# practice.net
KiCad netlist of a schematic drawn in EAGLE
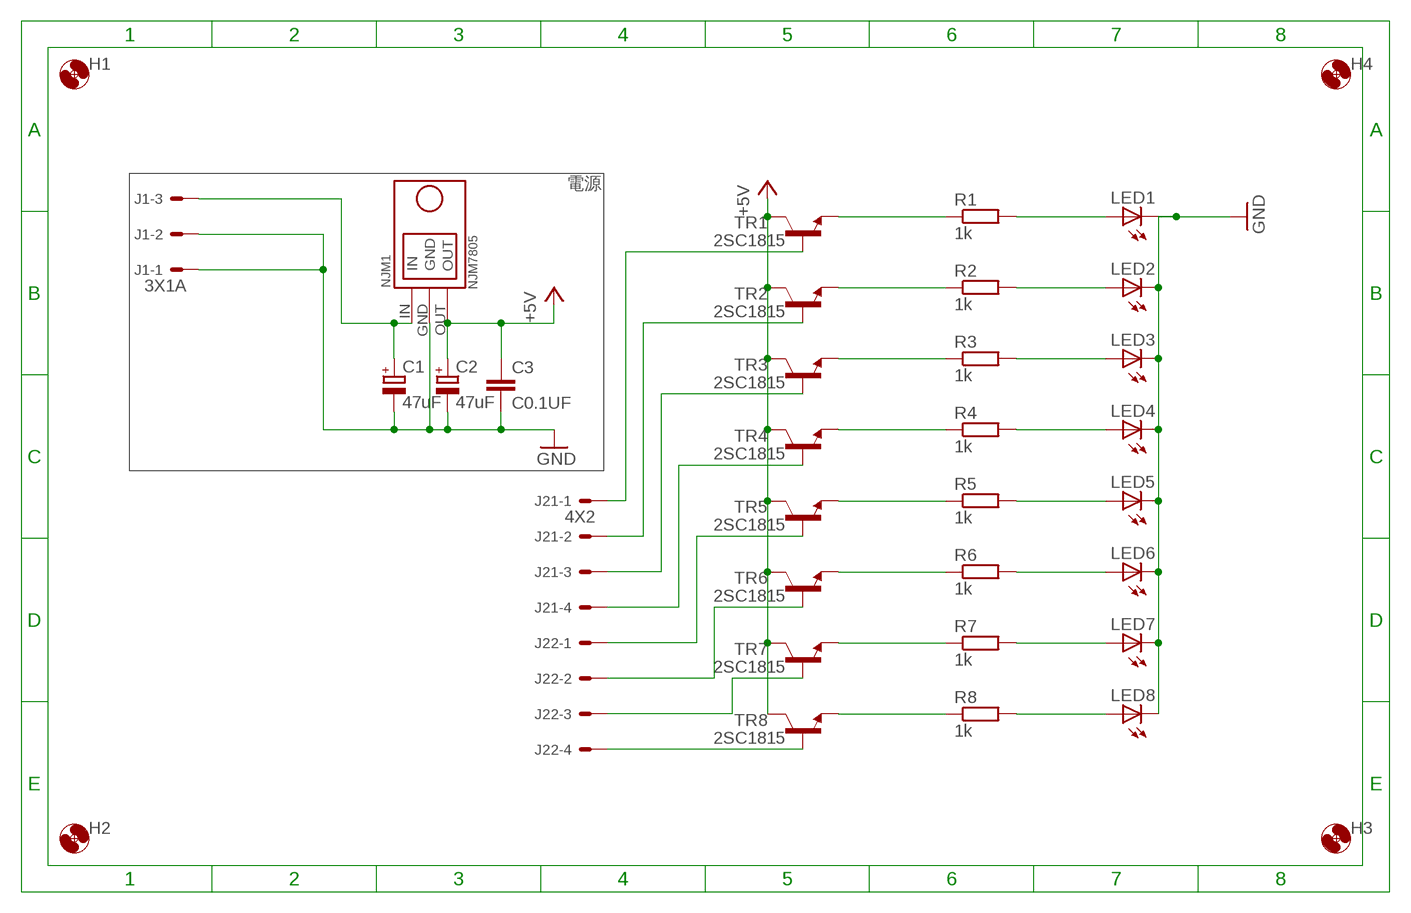
[diagram p0: schematic, sheet 1]

(export (version "E")
  (design (tool "Eeschema 10.0.6"))
  (components
    (comp (ref "C1")
      (value "47uF")
      (footprint "eagle-import:E2-5")
      (libsource (lib "eagle-import") (part "CPOL-EU2-5MM"))
    )
    (comp (ref "C2")
      (value "47uF")
      (footprint "eagle-import:E2-5")
      (libsource (lib "eagle-import") (part "CPOL-EU2-5MM"))
    )
    (comp (ref "C3")
      (value "C0.1UF")
      (footprint "eagle-import:C0.1UF")
      (libsource (lib "eagle-import") (part "C0.1UF"))
    )
    (comp (ref "H1")
      (value "HOLE3.3M3BOLT")
      (footprint "eagle-import:HOLE3.3")
      (libsource (lib "eagle-import") (part "HOLE3.3M3BOLT"))
    )
    (comp (ref "H2")
      (value "HOLE3.3M3BOLT")
      (footprint "eagle-import:HOLE3.3")
      (libsource (lib "eagle-import") (part "HOLE3.3M3BOLT"))
    )
    (comp (ref "H3")
      (value "HOLE3.3M3BOLT")
      (footprint "eagle-import:HOLE3.3")
      (libsource (lib "eagle-import") (part "HOLE3.3M3BOLT"))
    )
    (comp (ref "H4")
      (value "HOLE3.3M3BOLT")
      (footprint "eagle-import:HOLE3.3")
      (libsource (lib "eagle-import") (part "HOLE3.3M3BOLT"))
    )
    (comp (ref "J1")
      (value "3X1A")
      (footprint "eagle-import:37203-62A3-003")
      (libsource (lib "eagle-import") (part "3X1A"))
    )
    (comp (ref "J2")
      (value "4X2")
      (footprint "eagle-import:37208-62A3-004")
      (libsource (lib "eagle-import") (part "4X2"))
    )
    (comp (ref "LED1")
      (value "LED5MM")
      (footprint "eagle-import:LED5MM")
      (libsource (lib "eagle-import") (part "LED5MM"))
    )
    (comp (ref "LED2")
      (value "LED5MM")
      (footprint "eagle-import:LED5MM")
      (libsource (lib "eagle-import") (part "LED5MM"))
    )
    (comp (ref "LED3")
      (value "LED5MM")
      (footprint "eagle-import:LED5MM")
      (libsource (lib "eagle-import") (part "LED5MM"))
    )
    (comp (ref "LED4")
      (value "LED5MM")
      (footprint "eagle-import:LED5MM")
      (libsource (lib "eagle-import") (part "LED5MM"))
    )
    (comp (ref "LED5")
      (value "LED5MM")
      (footprint "eagle-import:LED5MM")
      (libsource (lib "eagle-import") (part "LED5MM"))
    )
    (comp (ref "LED6")
      (value "LED5MM")
      (footprint "eagle-import:LED5MM")
      (libsource (lib "eagle-import") (part "LED5MM"))
    )
    (comp (ref "LED7")
      (value "LED5MM")
      (footprint "eagle-import:LED5MM")
      (libsource (lib "eagle-import") (part "LED5MM"))
    )
    (comp (ref "LED8")
      (value "LED5MM")
      (footprint "eagle-import:LED5MM")
      (libsource (lib "eagle-import") (part "LED5MM"))
    )
    (comp (ref "NJM1")
      (value "NJM7805")
      (footprint "eagle-import:NJM7805")
      (libsource (lib "eagle-import") (part "NJM7805"))
    )
    (comp (ref "R1")
      (value "1k")
      (footprint "eagle-import:R3216W")
      (libsource (lib "eagle-import") (part "R-EU_R3216W"))
    )
    (comp (ref "R2")
      (value "1k")
      (footprint "eagle-import:R3216W")
      (libsource (lib "eagle-import") (part "R-EU_R3216W"))
    )
    (comp (ref "R3")
      (value "1k")
      (footprint "eagle-import:R3216W")
      (libsource (lib "eagle-import") (part "R-EU_R3216W"))
    )
    (comp (ref "R4")
      (value "1k")
      (footprint "eagle-import:R3216W")
      (libsource (lib "eagle-import") (part "R-EU_R3216W"))
    )
    (comp (ref "R5")
      (value "1k")
      (footprint "eagle-import:R3216W")
      (libsource (lib "eagle-import") (part "R-EU_R3216W"))
    )
    (comp (ref "R6")
      (value "1k")
      (footprint "eagle-import:R3216W")
      (libsource (lib "eagle-import") (part "R-EU_R3216W"))
    )
    (comp (ref "R7")
      (value "1k")
      (footprint "eagle-import:R3216W")
      (libsource (lib "eagle-import") (part "R-EU_R3216W"))
    )
    (comp (ref "R8")
      (value "1k")
      (footprint "eagle-import:R3216W")
      (libsource (lib "eagle-import") (part "R-EU_R3216W"))
    )
    (comp (ref "TR1")
      (value "2SC1815")
      (footprint "eagle-import:TO92-")
      (libsource (lib "eagle-import") (part "2SC1815"))
    )
    (comp (ref "TR2")
      (value "2SC1815")
      (footprint "eagle-import:TO92-")
      (libsource (lib "eagle-import") (part "2SC1815"))
    )
    (comp (ref "TR3")
      (value "2SC1815")
      (footprint "eagle-import:TO92-")
      (libsource (lib "eagle-import") (part "2SC1815"))
    )
    (comp (ref "TR4")
      (value "2SC1815")
      (footprint "eagle-import:TO92-")
      (libsource (lib "eagle-import") (part "2SC1815"))
    )
    (comp (ref "TR5")
      (value "2SC1815")
      (footprint "eagle-import:TO92-")
      (libsource (lib "eagle-import") (part "2SC1815"))
    )
    (comp (ref "TR6")
      (value "2SC1815")
      (footprint "eagle-import:TO92-")
      (libsource (lib "eagle-import") (part "2SC1815"))
    )
    (comp (ref "TR7")
      (value "2SC1815")
      (footprint "eagle-import:TO92-")
      (libsource (lib "eagle-import") (part "2SC1815"))
    )
    (comp (ref "TR8")
      (value "2SC1815")
      (footprint "eagle-import:TO92-")
      (libsource (lib "eagle-import") (part "2SC1815"))
    )
  )
  (nets
    (net (code "1") (name "+5V") (class "Default")
      (node (ref "C2") (pin "+") (pinfunction "+_+") (pintype "passive"))
      (node (ref "C3") (pin "1") (pinfunction "1_1") (pintype "passive"))
      (node (ref "NJM1") (pin "OUT") (pinfunction "OUT_OUT") (pintype "bidirectional"))
      (node (ref "TR1") (pin "C") (pinfunction "C_C") (pintype "passive"))
      (node (ref "TR2") (pin "C") (pinfunction "C_C") (pintype "passive"))
      (node (ref "TR3") (pin "C") (pinfunction "C_C") (pintype "passive"))
      (node (ref "TR4") (pin "C") (pinfunction "C_C") (pintype "passive"))
      (node (ref "TR5") (pin "C") (pinfunction "C_C") (pintype "passive"))
      (node (ref "TR6") (pin "C") (pinfunction "C_C") (pintype "passive"))
      (node (ref "TR7") (pin "C") (pinfunction "C_C") (pintype "passive"))
      (node (ref "TR8") (pin "C") (pinfunction "C_C") (pintype "passive"))
    )
    (net (code "2") (name "GND") (class "Default")
      (node (ref "C1") (pin "-") (pinfunction "-_-") (pintype "passive"))
      (node (ref "C2") (pin "-") (pinfunction "-_-") (pintype "passive"))
      (node (ref "C3") (pin "2") (pinfunction "2_2") (pintype "passive"))
      (node (ref "J1") (pin "1-1") (pinfunction "S_1-1") (pintype "passive"))
      (node (ref "J1") (pin "1-2") (pinfunction "S_1-2") (pintype "passive"))
      (node (ref "LED1") (pin "K") (pinfunction "C_K") (pintype "passive"))
      (node (ref "LED2") (pin "K") (pinfunction "C_K") (pintype "passive"))
      (node (ref "LED3") (pin "K") (pinfunction "C_K") (pintype "passive"))
      (node (ref "LED4") (pin "K") (pinfunction "C_K") (pintype "passive"))
      (node (ref "LED5") (pin "K") (pinfunction "C_K") (pintype "passive"))
      (node (ref "LED6") (pin "K") (pinfunction "C_K") (pintype "passive"))
      (node (ref "LED7") (pin "K") (pinfunction "C_K") (pintype "passive"))
      (node (ref "LED8") (pin "K") (pinfunction "C_K") (pintype "passive"))
      (node (ref "NJM1") (pin "GND") (pinfunction "GND_GND") (pintype "bidirectional"))
    )
    (net (code "3") (name "Net-(J1C-S)") (class "Default")
      (node (ref "C1") (pin "+") (pinfunction "+_+") (pintype "passive"))
      (node (ref "J1") (pin "1-3") (pinfunction "S_1-3") (pintype "passive"))
      (node (ref "NJM1") (pin "IN") (pinfunction "IN_IN") (pintype "bidirectional"))
    )
    (net (code "4") (name "Net-(J2A-S)") (class "Default")
      (node (ref "J2") (pin "1-1") (pinfunction "S_1-1") (pintype "passive"))
      (node (ref "TR1") (pin "B") (pinfunction "B_B") (pintype "passive"))
    )
    (net (code "5") (name "Net-(J2B-S)") (class "Default")
      (node (ref "J2") (pin "1-2") (pinfunction "S_1-2") (pintype "passive"))
      (node (ref "TR2") (pin "B") (pinfunction "B_B") (pintype "passive"))
    )
    (net (code "6") (name "Net-(J2C-S)") (class "Default")
      (node (ref "J2") (pin "1-3") (pinfunction "S_1-3") (pintype "passive"))
      (node (ref "TR3") (pin "B") (pinfunction "B_B") (pintype "passive"))
    )
    (net (code "7") (name "Net-(J2D-S)") (class "Default")
      (node (ref "J2") (pin "1-4") (pinfunction "S_1-4") (pintype "passive"))
      (node (ref "TR4") (pin "B") (pinfunction "B_B") (pintype "passive"))
    )
    (net (code "8") (name "Net-(J2E-S)") (class "Default")
      (node (ref "J2") (pin "2-1") (pinfunction "S_2-1") (pintype "passive"))
      (node (ref "TR5") (pin "B") (pinfunction "B_B") (pintype "passive"))
    )
    (net (code "9") (name "Net-(J2F-S)") (class "Default")
      (node (ref "J2") (pin "2-2") (pinfunction "S_2-2") (pintype "passive"))
      (node (ref "TR6") (pin "B") (pinfunction "B_B") (pintype "passive"))
    )
    (net (code "10") (name "Net-(J2G-S)") (class "Default")
      (node (ref "J2") (pin "2-3") (pinfunction "S_2-3") (pintype "passive"))
      (node (ref "TR7") (pin "B") (pinfunction "B_B") (pintype "passive"))
    )
    (net (code "11") (name "Net-(J2H-S)") (class "Default")
      (node (ref "J2") (pin "2-4") (pinfunction "S_2-4") (pintype "passive"))
      (node (ref "TR8") (pin "B") (pinfunction "B_B") (pintype "passive"))
    )
    (net (code "12") (name "Net-(LED1-PadA)") (class "Default")
      (node (ref "LED1") (pin "A") (pinfunction "A_A") (pintype "passive"))
      (node (ref "R1") (pin "2") (pinfunction "2_2") (pintype "passive"))
    )
    (net (code "13") (name "Net-(LED2-PadA)") (class "Default")
      (node (ref "LED2") (pin "A") (pinfunction "A_A") (pintype "passive"))
      (node (ref "R2") (pin "2") (pinfunction "2_2") (pintype "passive"))
    )
    (net (code "14") (name "Net-(LED3-PadA)") (class "Default")
      (node (ref "LED3") (pin "A") (pinfunction "A_A") (pintype "passive"))
      (node (ref "R3") (pin "2") (pinfunction "2_2") (pintype "passive"))
    )
    (net (code "15") (name "Net-(LED4-PadA)") (class "Default")
      (node (ref "LED4") (pin "A") (pinfunction "A_A") (pintype "passive"))
      (node (ref "R4") (pin "2") (pinfunction "2_2") (pintype "passive"))
    )
    (net (code "16") (name "Net-(LED5-PadA)") (class "Default")
      (node (ref "LED5") (pin "A") (pinfunction "A_A") (pintype "passive"))
      (node (ref "R5") (pin "2") (pinfunction "2_2") (pintype "passive"))
    )
    (net (code "17") (name "Net-(LED6-PadA)") (class "Default")
      (node (ref "LED6") (pin "A") (pinfunction "A_A") (pintype "passive"))
      (node (ref "R6") (pin "2") (pinfunction "2_2") (pintype "passive"))
    )
    (net (code "18") (name "Net-(LED7-PadA)") (class "Default")
      (node (ref "LED7") (pin "A") (pinfunction "A_A") (pintype "passive"))
      (node (ref "R7") (pin "2") (pinfunction "2_2") (pintype "passive"))
    )
    (net (code "19") (name "Net-(LED8-PadA)") (class "Default")
      (node (ref "LED8") (pin "A") (pinfunction "A_A") (pintype "passive"))
      (node (ref "R8") (pin "2") (pinfunction "2_2") (pintype "passive"))
    )
    (net (code "20") (name "Net-(R1-Pad1)") (class "Default")
      (node (ref "R1") (pin "1") (pinfunction "1_1") (pintype "passive"))
      (node (ref "TR1") (pin "E") (pinfunction "E_E") (pintype "passive"))
    )
    (net (code "21") (name "Net-(R2-Pad1)") (class "Default")
      (node (ref "R2") (pin "1") (pinfunction "1_1") (pintype "passive"))
      (node (ref "TR2") (pin "E") (pinfunction "E_E") (pintype "passive"))
    )
    (net (code "22") (name "Net-(R3-Pad1)") (class "Default")
      (node (ref "R3") (pin "1") (pinfunction "1_1") (pintype "passive"))
      (node (ref "TR3") (pin "E") (pinfunction "E_E") (pintype "passive"))
    )
    (net (code "23") (name "Net-(R4-Pad1)") (class "Default")
      (node (ref "R4") (pin "1") (pinfunction "1_1") (pintype "passive"))
      (node (ref "TR4") (pin "E") (pinfunction "E_E") (pintype "passive"))
    )
    (net (code "24") (name "Net-(R5-Pad1)") (class "Default")
      (node (ref "R5") (pin "1") (pinfunction "1_1") (pintype "passive"))
      (node (ref "TR5") (pin "E") (pinfunction "E_E") (pintype "passive"))
    )
    (net (code "25") (name "Net-(R6-Pad1)") (class "Default")
      (node (ref "R6") (pin "1") (pinfunction "1_1") (pintype "passive"))
      (node (ref "TR6") (pin "E") (pinfunction "E_E") (pintype "passive"))
    )
    (net (code "26") (name "Net-(R7-Pad1)") (class "Default")
      (node (ref "R7") (pin "1") (pinfunction "1_1") (pintype "passive"))
      (node (ref "TR7") (pin "E") (pinfunction "E_E") (pintype "passive"))
    )
    (net (code "27") (name "Net-(R8-Pad1)") (class "Default")
      (node (ref "R8") (pin "1") (pinfunction "1_1") (pintype "passive"))
      (node (ref "TR8") (pin "E") (pinfunction "E_E") (pintype "passive"))
    )
  )
)
